# Magnetic_Stage.net
KiCad netlist of a schematic drawn in Altium Designer
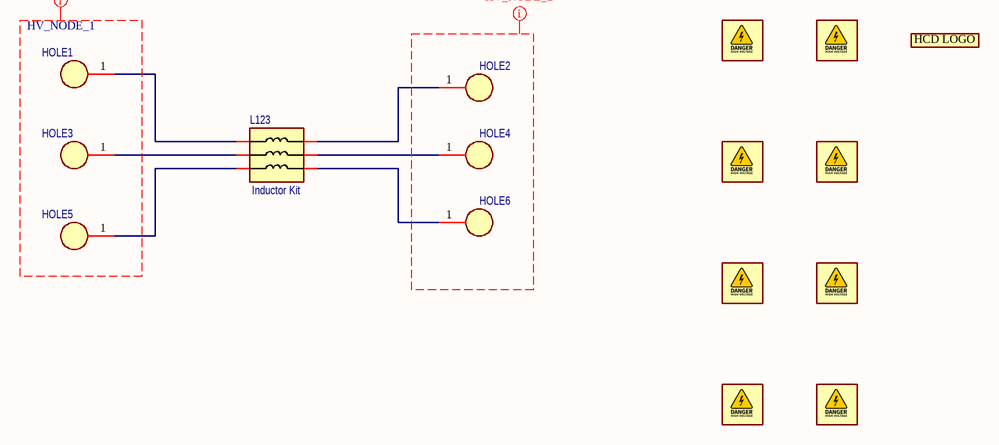
[diagram p0: Magnetic_Stage.SchDoc]

(export (version "E")
  (design (tool "Eeschema 10.0.6"))
  (components
    (comp (ref "HOLE1")
      (value "HOLE_CIRC_1POS_NO_BOM")
      (footprint "HOLE_M4_4.5_12SQ")
      (description "4.5mm hole size 12X12 mm hole for M4")
      (libsource (lib "HCD_Database_Libs") (part "HOLE_CIRC_1POS_NO_BOM"))
    )
    (comp (ref "HOLE2")
      (value "HOLE_CIRC_1POS_NO_BOM")
      (footprint "HOLE_M4_4.5_12SQ")
      (description "4.5mm hole size 12X12 mm hole for M4")
      (libsource (lib "HCD_Database_Libs") (part "HOLE_CIRC_1POS_NO_BOM"))
    )
    (comp (ref "HOLE3")
      (value "HOLE_CIRC_1POS_NO_BOM")
      (footprint "HOLE_M4_4.5_12SQ")
      (description "4.5mm hole size 12X12 mm hole for M4")
      (libsource (lib "HCD_Database_Libs") (part "HOLE_CIRC_1POS_NO_BOM"))
    )
    (comp (ref "HOLE4")
      (value "HOLE_CIRC_1POS_NO_BOM")
      (footprint "HOLE_M4_4.5_12SQ")
      (description "4.5mm hole size 12X12 mm hole for M4")
      (libsource (lib "HCD_Database_Libs") (part "HOLE_CIRC_1POS_NO_BOM"))
    )
    (comp (ref "HOLE5")
      (value "HOLE_CIRC_1POS_NO_BOM")
      (footprint "HOLE_M4_4.5_12SQ")
      (description "4.5mm hole size 12X12 mm hole for M4")
      (libsource (lib "HCD_Database_Libs") (part "HOLE_CIRC_1POS_NO_BOM"))
    )
    (comp (ref "HOLE6")
      (value "HOLE_CIRC_1POS_NO_BOM")
      (footprint "HOLE_M4_4.5_12SQ")
      (description "4.5mm hole size 12X12 mm hole for M4")
      (libsource (lib "HCD_Database_Libs") (part "HOLE_CIRC_1POS_NO_BOM"))
    )
    (comp (ref "L123")
      (value "Inductor_3ph")
      (footprint "IND_3PH_SET_20A")
      (description "CORE Electronic DT6 235uH Inductor 3 kit")
      (fields (field (name "MANUFACTURER") "Core Electronic") (field (name "TOLERANCE") "±12%"))
      (libsource (lib "HCD_Database_Libs") (part "Inductor_3ph"))
    )
    (comp (ref "LOGO1")
      (value "HIGH_VOLTAGE_LOGO")
      (footprint "HV_LOGO")
      (description "Silk Screen High Voltage Logo")
      (libsource (lib "HCD_Database_Libs") (part "HIGH_VOLTAGE_LOGO"))
    )
    (comp (ref "LOGO2")
      (value "HIGH_VOLTAGE_LOGO")
      (footprint "HV_LOGO")
      (description "Silk Screen High Voltage Logo")
      (libsource (lib "HCD_Database_Libs") (part "HIGH_VOLTAGE_LOGO"))
    )
    (comp (ref "LOGO3")
      (value "HIGH_VOLTAGE_LOGO")
      (footprint "HV_LOGO")
      (description "Silk Screen High Voltage Logo")
      (libsource (lib "HCD_Database_Libs") (part "HIGH_VOLTAGE_LOGO"))
    )
    (comp (ref "LOGO4")
      (value "HIGH_VOLTAGE_LOGO")
      (footprint "HV_LOGO")
      (description "Silk Screen High Voltage Logo")
      (libsource (lib "HCD_Database_Libs") (part "HIGH_VOLTAGE_LOGO"))
    )
    (comp (ref "LOGO5")
      (value "HIGH_VOLTAGE_LOGO")
      (footprint "HV_LOGO")
      (description "Silk Screen High Voltage Logo")
      (libsource (lib "HCD_Database_Libs") (part "HIGH_VOLTAGE_LOGO"))
    )
    (comp (ref "LOGO6")
      (value "HIGH_VOLTAGE_LOGO")
      (footprint "HV_LOGO")
      (description "Silk Screen High Voltage Logo")
      (libsource (lib "HCD_Database_Libs") (part "HIGH_VOLTAGE_LOGO"))
    )
    (comp (ref "LOGO7")
      (value "HIGH_VOLTAGE_LOGO")
      (footprint "HV_LOGO")
      (description "Silk Screen High Voltage Logo")
      (libsource (lib "HCD_Database_Libs") (part "HIGH_VOLTAGE_LOGO"))
    )
    (comp (ref "LOGO8")
      (value "HIGH_VOLTAGE_LOGO")
      (footprint "HV_LOGO")
      (description "Silk Screen High Voltage Logo")
      (libsource (lib "HCD_Database_Libs") (part "HIGH_VOLTAGE_LOGO"))
    )
    (comp (ref "LOGO1000")
      (value "HCD_LOGO")
      (footprint "HCD_LOGO_V1")
      (description "Hamit Can Dinç LOGO")
      (libsource (lib "HCD_Database_Libs") (part "HCD_LOGO"))
    )
  )
  (nets
    (net (code "1") (name "Net-(HOLE1-Pad1)") (class "Default")
      (node (ref "HOLE1") (pin "1") (pinfunction "1_1") (pintype "passive"))
      (node (ref "L123") (pin "1") (pinfunction "1_1") (pintype "passive"))
    )
    (net (code "2") (name "Net-(HOLE2-Pad1)") (class "Default")
      (node (ref "HOLE2") (pin "1") (pinfunction "1_1") (pintype "passive"))
      (node (ref "L123") (pin "2") (pinfunction "2_2") (pintype "passive"))
    )
    (net (code "3") (name "Net-(HOLE3-Pad1)") (class "Default")
      (node (ref "HOLE3") (pin "1") (pinfunction "1_1") (pintype "passive"))
      (node (ref "L123") (pin "3") (pinfunction "3_3") (pintype "passive"))
    )
    (net (code "4") (name "Net-(HOLE4-Pad1)") (class "Default")
      (node (ref "HOLE4") (pin "1") (pinfunction "1_1") (pintype "passive"))
      (node (ref "L123") (pin "4") (pinfunction "4_4") (pintype "passive"))
    )
    (net (code "5") (name "Net-(HOLE5-Pad1)") (class "Default")
      (node (ref "HOLE5") (pin "1") (pinfunction "1_1") (pintype "passive"))
      (node (ref "L123") (pin "5") (pinfunction "5_5") (pintype "passive"))
    )
    (net (code "6") (name "Net-(HOLE6-Pad1)") (class "Default")
      (node (ref "HOLE6") (pin "1") (pinfunction "1_1") (pintype "passive"))
      (node (ref "L123") (pin "6") (pinfunction "6_6") (pintype "passive"))
    )
  )
)
